# ItsyBitsy_Basic.net
KiCad netlist of a schematic drawn in EAGLE
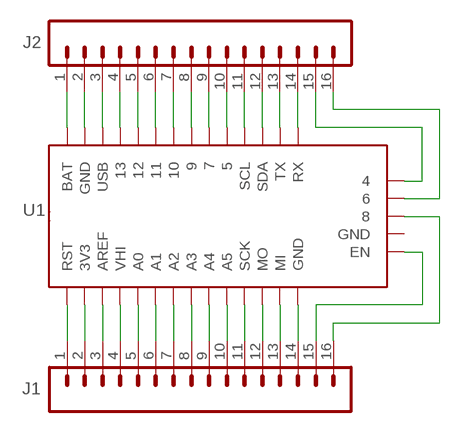
[diagram p0: schematic, sheet 1]

(export (version "E")
  (design (tool "Eeschema 10.0.6"))
  (components
    (comp (ref "J1")
      (value "CONN_161X16_NO_SILK")
      (footprint "eagle-import:1X16_NO_SILK")
      (libsource (lib "eagle-import") (part "CONN_161X16_NO_SILK"))
    )
    (comp (ref "J2")
      (value "CONN_161X16_NO_SILK")
      (footprint "eagle-import:1X16_NO_SILK")
      (libsource (lib "eagle-import") (part "CONN_161X16_NO_SILK"))
    )
    (comp (ref "U1")
      (value "ITSYBITSY-32U4-3V")
      (footprint "eagle-import:ITSYBITYS-32U4")
      (libsource (lib "eagle-import") (part "ITSYBITSY-32U4-3V"))
    )
  )
  (nets
    (net (code "1") (name "/GND") (class "Default")
      (node (ref "U1") (pin "P$16") (pinfunction "GND_P$16") (pintype "power_in"))
    )
    (net (code "2") (name "Net-(J1-Pad14)") (class "Default")
      (node (ref "J1") (pin "14") (pinfunction "14_14") (pintype "passive"))
      (node (ref "U1") (pin "P$14") (pinfunction "GND_P$14") (pintype "power_in"))
    )
    (net (code "3") (name "Net-(J2-Pad2)") (class "Default")
      (node (ref "J2") (pin "2") (pinfunction "2_2") (pintype "passive"))
      (node (ref "U1") (pin "P$32") (pinfunction "GND_P$32") (pintype "power_in"))
    )
    (net (code "4") (name "Net-(U1-3V3)") (class "Default")
      (node (ref "J1") (pin "2") (pinfunction "2_2") (pintype "passive"))
      (node (ref "U1") (pin "P$2") (pinfunction "3V3_P$2") (pintype "power_in"))
    )
    (net (code "5") (name "Net-(U1-4)") (class "Default")
      (node (ref "J2") (pin "15") (pinfunction "15_15") (pintype "passive"))
      (node (ref "U1") (pin "P$19") (pinfunction "4_P$19") (pintype "bidirectional"))
    )
    (net (code "6") (name "Net-(U1-5)") (class "Default")
      (node (ref "J2") (pin "10") (pinfunction "10_10") (pintype "passive"))
      (node (ref "U1") (pin "P$24") (pinfunction "5_P$24") (pintype "bidirectional"))
    )
    (net (code "7") (name "Net-(U1-6)") (class "Default")
      (node (ref "J2") (pin "16") (pinfunction "16_16") (pintype "passive"))
      (node (ref "U1") (pin "P$18") (pinfunction "6_P$18") (pintype "bidirectional"))
    )
    (net (code "8") (name "Net-(U1-7)") (class "Default")
      (node (ref "J2") (pin "9") (pinfunction "9_9") (pintype "passive"))
      (node (ref "U1") (pin "P$25") (pinfunction "7_P$25") (pintype "bidirectional"))
    )
    (net (code "9") (name "Net-(U1-8)") (class "Default")
      (node (ref "J1") (pin "16") (pinfunction "16_16") (pintype "passive"))
      (node (ref "U1") (pin "P$17") (pinfunction "8_P$17") (pintype "bidirectional"))
    )
    (net (code "10") (name "Net-(U1-9)") (class "Default")
      (node (ref "J2") (pin "8") (pinfunction "8_8") (pintype "passive"))
      (node (ref "U1") (pin "P$26") (pinfunction "9_P$26") (pintype "bidirectional"))
    )
    (net (code "11") (name "Net-(U1-10)") (class "Default")
      (node (ref "J2") (pin "7") (pinfunction "7_7") (pintype "passive"))
      (node (ref "U1") (pin "P$27") (pinfunction "10_P$27") (pintype "bidirectional"))
    )
    (net (code "12") (name "Net-(U1-11)") (class "Default")
      (node (ref "J2") (pin "6") (pinfunction "6_6") (pintype "passive"))
      (node (ref "U1") (pin "P$28") (pinfunction "11_P$28") (pintype "bidirectional"))
    )
    (net (code "13") (name "Net-(U1-12)") (class "Default")
      (node (ref "J2") (pin "5") (pinfunction "5_5") (pintype "passive"))
      (node (ref "U1") (pin "P$29") (pinfunction "12_P$29") (pintype "bidirectional"))
    )
    (net (code "14") (name "Net-(U1-13)") (class "Default")
      (node (ref "J2") (pin "4") (pinfunction "4_4") (pintype "passive"))
      (node (ref "U1") (pin "P$30") (pinfunction "13_P$30") (pintype "bidirectional"))
    )
    (net (code "15") (name "Net-(U1-A0)") (class "Default")
      (node (ref "J1") (pin "5") (pinfunction "5_5") (pintype "passive"))
      (node (ref "U1") (pin "P$5") (pinfunction "A0_P$5") (pintype "bidirectional"))
    )
    (net (code "16") (name "Net-(U1-A1)") (class "Default")
      (node (ref "J1") (pin "6") (pinfunction "6_6") (pintype "passive"))
      (node (ref "U1") (pin "P$6") (pinfunction "A1_P$6") (pintype "bidirectional"))
    )
    (net (code "17") (name "Net-(U1-A2)") (class "Default")
      (node (ref "J1") (pin "7") (pinfunction "7_7") (pintype "passive"))
      (node (ref "U1") (pin "P$7") (pinfunction "A2_P$7") (pintype "bidirectional"))
    )
    (net (code "18") (name "Net-(U1-A3)") (class "Default")
      (node (ref "J1") (pin "8") (pinfunction "8_8") (pintype "passive"))
      (node (ref "U1") (pin "P$8") (pinfunction "A3_P$8") (pintype "bidirectional"))
    )
    (net (code "19") (name "Net-(U1-A4)") (class "Default")
      (node (ref "J1") (pin "9") (pinfunction "9_9") (pintype "passive"))
      (node (ref "U1") (pin "P$9") (pinfunction "A4_P$9") (pintype "bidirectional"))
    )
    (net (code "20") (name "Net-(U1-A5)") (class "Default")
      (node (ref "J1") (pin "10") (pinfunction "10_10") (pintype "passive"))
      (node (ref "U1") (pin "P$10") (pinfunction "A5_P$10") (pintype "bidirectional"))
    )
    (net (code "21") (name "Net-(U1-AREF)") (class "Default")
      (node (ref "J1") (pin "3") (pinfunction "3_3") (pintype "passive"))
      (node (ref "U1") (pin "P$3") (pinfunction "AREF_P$3") (pintype "input"))
    )
    (net (code "22") (name "Net-(U1-BAT)") (class "Default")
      (node (ref "J2") (pin "1") (pinfunction "1_1") (pintype "passive"))
      (node (ref "U1") (pin "P$33") (pinfunction "BAT_P$33") (pintype "power_in"))
    )
    (net (code "23") (name "Net-(U1-EN)") (class "Default")
      (node (ref "J1") (pin "15") (pinfunction "15_15") (pintype "passive"))
      (node (ref "U1") (pin "P$15") (pinfunction "EN_P$15") (pintype "input"))
    )
    (net (code "24") (name "Net-(U1-MI)") (class "Default")
      (node (ref "J1") (pin "13") (pinfunction "13_13") (pintype "passive"))
      (node (ref "U1") (pin "P$13") (pinfunction "MI_P$13") (pintype "bidirectional"))
    )
    (net (code "25") (name "Net-(U1-MO)") (class "Default")
      (node (ref "J1") (pin "12") (pinfunction "12_12") (pintype "passive"))
      (node (ref "U1") (pin "P$12") (pinfunction "MO_P$12") (pintype "bidirectional"))
    )
    (net (code "26") (name "Net-(U1-RST)") (class "Default")
      (node (ref "J1") (pin "1") (pinfunction "1_1") (pintype "passive"))
      (node (ref "U1") (pin "P$1") (pinfunction "RST_P$1") (pintype "bidirectional"))
    )
    (net (code "27") (name "Net-(U1-RX)") (class "Default")
      (node (ref "J2") (pin "14") (pinfunction "14_14") (pintype "passive"))
      (node (ref "U1") (pin "P$20") (pinfunction "RX_P$20") (pintype "bidirectional"))
    )
    (net (code "28") (name "Net-(U1-SCK)") (class "Default")
      (node (ref "J1") (pin "11") (pinfunction "11_11") (pintype "passive"))
      (node (ref "U1") (pin "P$11") (pinfunction "SCK_P$11") (pintype "bidirectional"))
    )
    (net (code "29") (name "Net-(U1-SCL)") (class "Default")
      (node (ref "J2") (pin "11") (pinfunction "11_11") (pintype "passive"))
      (node (ref "U1") (pin "P$23") (pinfunction "SCL_P$23") (pintype "bidirectional"))
    )
    (net (code "30") (name "Net-(U1-SDA)") (class "Default")
      (node (ref "J2") (pin "12") (pinfunction "12_12") (pintype "passive"))
      (node (ref "U1") (pin "P$22") (pinfunction "SDA_P$22") (pintype "bidirectional"))
    )
    (net (code "31") (name "Net-(U1-TX)") (class "Default")
      (node (ref "J2") (pin "13") (pinfunction "13_13") (pintype "passive"))
      (node (ref "U1") (pin "P$21") (pinfunction "TX_P$21") (pintype "bidirectional"))
    )
    (net (code "32") (name "Net-(U1-USB)") (class "Default")
      (node (ref "J2") (pin "3") (pinfunction "3_3") (pintype "passive"))
      (node (ref "U1") (pin "P$31") (pinfunction "USB_P$31") (pintype "power_in"))
    )
    (net (code "33") (name "Net-(U1-VHI)") (class "Default")
      (node (ref "J1") (pin "4") (pinfunction "4_4") (pintype "passive"))
      (node (ref "U1") (pin "P$4") (pinfunction "VHI_P$4") (pintype "power_in"))
    )
  )
)
